# merak.net
KiCad netlist of a schematic drawn in EAGLE
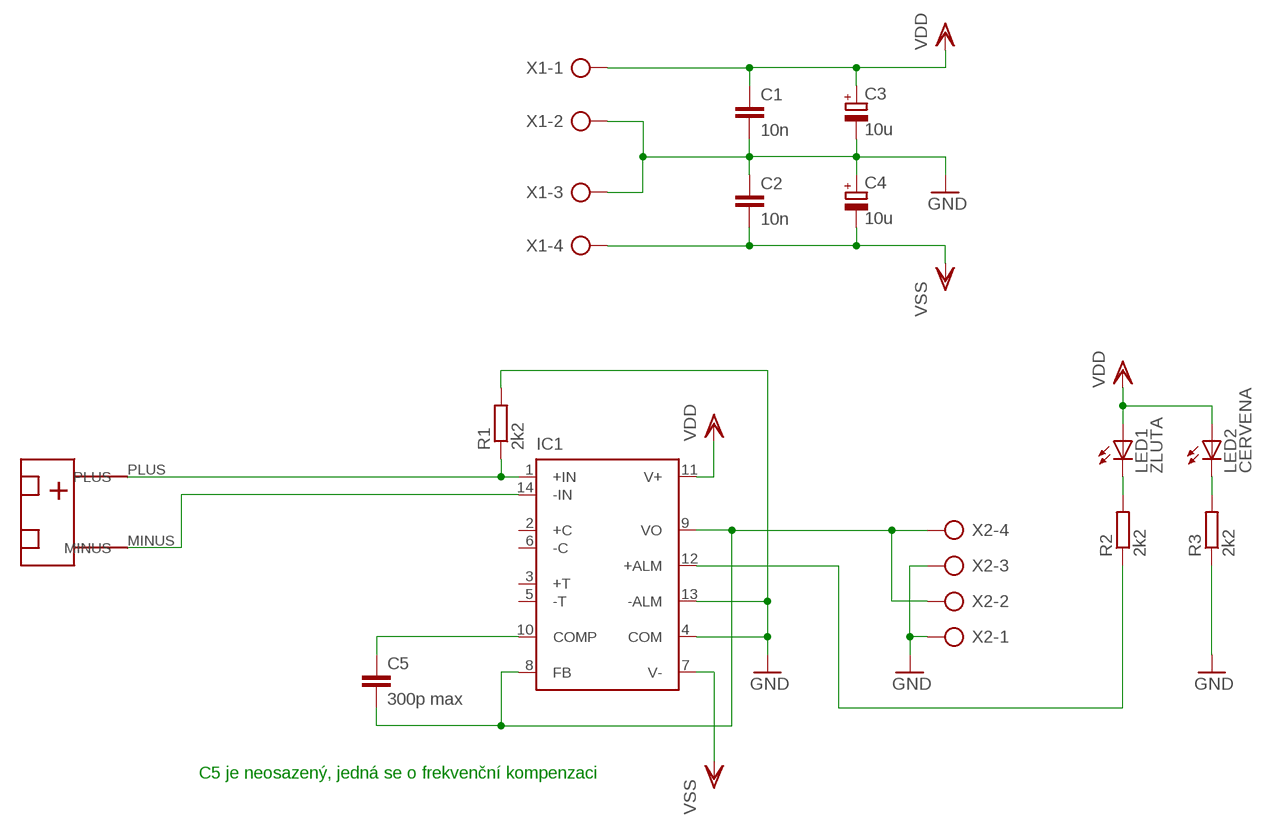
[diagram p0: schematic, sheet 1]

(export (version "E")
  (design (tool "Eeschema 10.0.6"))
  (components
    (comp (ref "C1")
      (value "10n")
      (footprint "eagle-import:C0805")
      (libsource (lib "eagle-import") (part "C-EUC0805"))
    )
    (comp (ref "C2")
      (value "10n")
      (footprint "eagle-import:C0805")
      (libsource (lib "eagle-import") (part "C-EUC0805"))
    )
    (comp (ref "C3")
      (value "10u")
      (footprint "eagle-import:E2,5-5")
      (libsource (lib "eagle-import") (part "CPOL-EUE2.5-5"))
    )
    (comp (ref "C4")
      (value "10u")
      (footprint "eagle-import:E2,5-5")
      (libsource (lib "eagle-import") (part "CPOL-EUE2.5-5"))
    )
    (comp (ref "C5")
      (value "300p max")
      (footprint "eagle-import:C0805")
      (libsource (lib "eagle-import") (part "C-EUC0805"))
    )
    (comp (ref "IC1")
      (value "AD595")
      (footprint "eagle-import:DIL14")
      (fields (field (name "MPN") "AD595AQ"))
      (libsource (lib "eagle-import") (part "AD595"))
    )
    (comp (ref "LED1")
      (value "ZLUTA")
      (footprint "eagle-import:LED3MM")
      (libsource (lib "eagle-import") (part "LED3MM"))
    )
    (comp (ref "LED2")
      (value "CERVENA")
      (footprint "eagle-import:LED3MM")
      (libsource (lib "eagle-import") (part "LED3MM"))
    )
    (comp (ref "R1")
      (value "2k2")
      (footprint "eagle-import:R0805")
      (libsource (lib "eagle-import") (part "R-EU_R0805"))
    )
    (comp (ref "R2")
      (value "2k2")
      (footprint "eagle-import:R0805")
      (libsource (lib "eagle-import") (part "R-EU_R0805"))
    )
    (comp (ref "R3")
      (value "2k2")
      (footprint "eagle-import:R0805")
      (libsource (lib "eagle-import") (part "R-EU_R0805"))
    )
    (comp (ref "U$1")
      (value "TERM_ZAS")
      (footprint "eagle-import:TERM_ZAS")
      (libsource (lib "eagle-import") (part "TERM_ZAS"))
    )
    (comp (ref "X1")
      (value "AK300/4")
      (footprint "eagle-import:AK300_4")
      (libsource (lib "eagle-import") (part "AK300/4"))
    )
    (comp (ref "X2")
      (value "AK300/4")
      (footprint "eagle-import:AK300_4")
      (libsource (lib "eagle-import") (part "AK300/4"))
    )
  )
  (nets
    (net (code "1") (name "GND") (class "Default")
      (node (ref "C1") (pin "2") (pinfunction "2_2") (pintype "passive"))
      (node (ref "C2") (pin "1") (pinfunction "1_1") (pintype "passive"))
      (node (ref "C3") (pin "-") (pinfunction "-_-") (pintype "passive"))
      (node (ref "C4") (pin "+") (pinfunction "+_+") (pintype "passive"))
      (node (ref "IC1") (pin "13") (pinfunction "-ALM_13") (pintype "passive"))
      (node (ref "IC1") (pin "4") (pinfunction "COM_4") (pintype "power_in"))
      (node (ref "R1") (pin "2") (pinfunction "2_2") (pintype "passive"))
      (node (ref "R3") (pin "1") (pinfunction "1_1") (pintype "passive"))
      (node (ref "X1") (pin "2") (pinfunction "KL_2") (pintype "passive"))
      (node (ref "X1") (pin "3") (pinfunction "KL_3") (pintype "passive"))
      (node (ref "X2") (pin "1") (pinfunction "KL_1") (pintype "passive"))
      (node (ref "X2") (pin "3") (pinfunction "KL_3") (pintype "passive"))
    )
    (net (code "2") (name "Net-(IC1-+ALM)") (class "Default")
      (node (ref "IC1") (pin "12") (pinfunction "+ALM_12") (pintype "passive"))
      (node (ref "R2") (pin "1") (pinfunction "1_1") (pintype "passive"))
    )
    (net (code "3") (name "Net-(IC1-+IN)") (class "Default")
      (node (ref "IC1") (pin "1") (pinfunction "+IN_1") (pintype "input"))
      (node (ref "R1") (pin "1") (pinfunction "1_1") (pintype "passive"))
      (node (ref "U$1") (pin "PLUS") (pinfunction "PLUS_PLUS") (pintype "passive"))
    )
    (net (code "4") (name "Net-(IC1--IN)") (class "Default")
      (node (ref "IC1") (pin "14") (pinfunction "-IN_14") (pintype "input"))
      (node (ref "U$1") (pin "MINUS") (pinfunction "MINUS_MINUS") (pintype "passive"))
    )
    (net (code "5") (name "Net-(IC1-COMP)") (class "Default")
      (node (ref "C5") (pin "1") (pinfunction "1_1") (pintype "passive"))
      (node (ref "IC1") (pin "10") (pinfunction "COMP_10") (pintype "passive"))
    )
    (net (code "6") (name "Net-(IC1-FB)") (class "Default")
      (node (ref "C5") (pin "2") (pinfunction "2_2") (pintype "passive"))
      (node (ref "IC1") (pin "8") (pinfunction "FB_8") (pintype "passive"))
      (node (ref "IC1") (pin "9") (pinfunction "VO_9") (pintype "output"))
      (node (ref "X2") (pin "2") (pinfunction "KL_2") (pintype "passive"))
      (node (ref "X2") (pin "4") (pinfunction "KL_4") (pintype "passive"))
    )
    (net (code "7") (name "Net-(LED1-C)") (class "Default")
      (node (ref "LED1") (pin "K") (pinfunction "C_K") (pintype "passive"))
      (node (ref "R2") (pin "2") (pinfunction "2_2") (pintype "passive"))
    )
    (net (code "8") (name "Net-(LED2-C)") (class "Default")
      (node (ref "LED2") (pin "K") (pinfunction "C_K") (pintype "passive"))
      (node (ref "R3") (pin "2") (pinfunction "2_2") (pintype "passive"))
    )
    (net (code "9") (name "VDD") (class "Default")
      (node (ref "C1") (pin "1") (pinfunction "1_1") (pintype "passive"))
      (node (ref "C3") (pin "+") (pinfunction "+_+") (pintype "passive"))
      (node (ref "IC1") (pin "11") (pinfunction "V+_11") (pintype "power_in"))
      (node (ref "LED1") (pin "A") (pinfunction "A_A") (pintype "passive"))
      (node (ref "LED2") (pin "A") (pinfunction "A_A") (pintype "passive"))
      (node (ref "X1") (pin "1") (pinfunction "KL_1") (pintype "passive"))
    )
    (net (code "10") (name "VSS") (class "Default")
      (node (ref "C2") (pin "2") (pinfunction "2_2") (pintype "passive"))
      (node (ref "C4") (pin "-") (pinfunction "-_-") (pintype "passive"))
      (node (ref "IC1") (pin "7") (pinfunction "V-_7") (pintype "power_in"))
      (node (ref "X1") (pin "4") (pinfunction "KL_4") (pintype "passive"))
    )
    (net (code "11") (name "unconnected-(IC1-+C-Pad2)") (class "Default")
      (node (ref "IC1") (pin "2") (pinfunction "+C_2") (pintype "input"))
    )
    (net (code "12") (name "unconnected-(IC1-+T-Pad3)") (class "Default")
      (node (ref "IC1") (pin "3") (pinfunction "+T_3") (pintype "passive"))
    )
    (net (code "13") (name "unconnected-(IC1--C-Pad6)") (class "Default")
      (node (ref "IC1") (pin "6") (pinfunction "-C_6") (pintype "input"))
    )
    (net (code "14") (name "unconnected-(IC1--T-Pad5)") (class "Default")
      (node (ref "IC1") (pin "5") (pinfunction "-T_5") (pintype "passive"))
    )
  )
)
